# SD.net
KiCad netlist of a schematic drawn in EAGLE
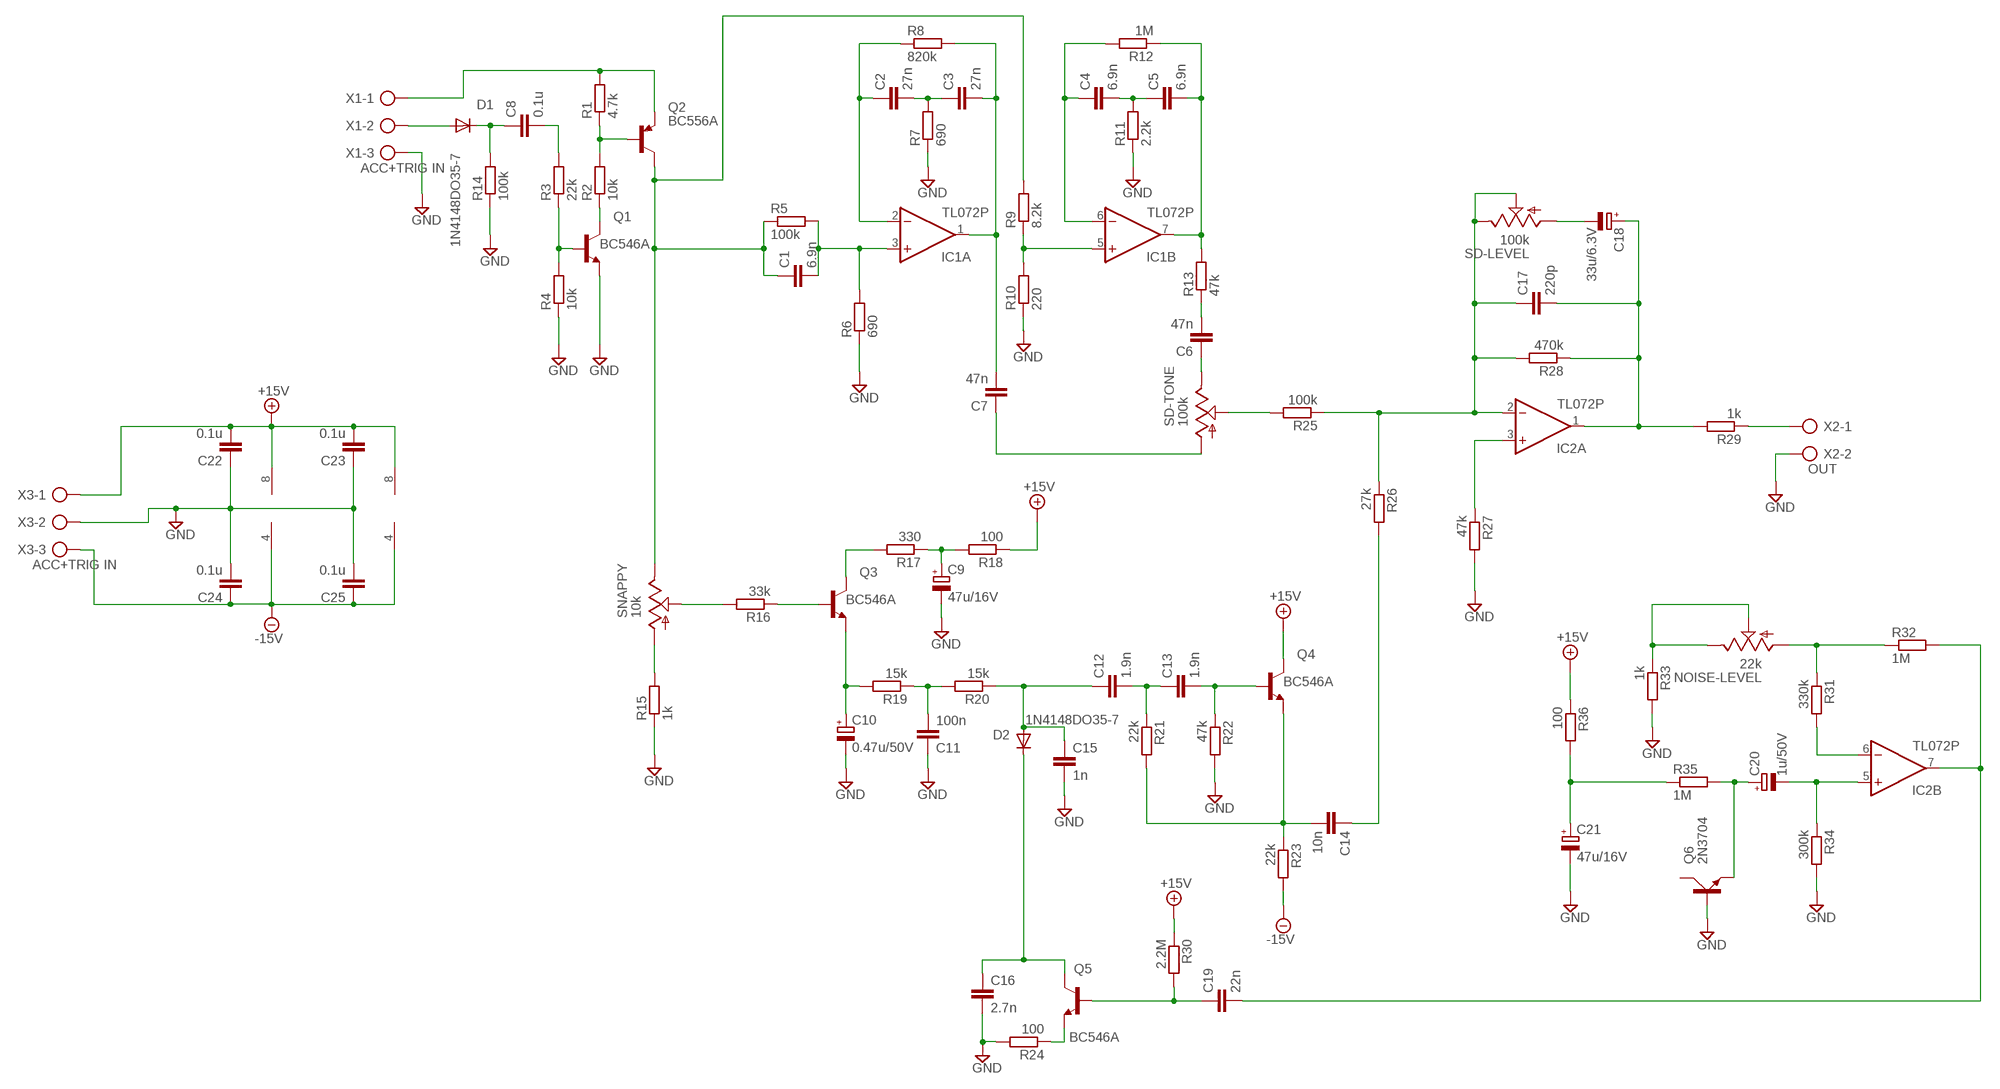
[diagram p0: schematic, sheet 1]

(export (version "E")
  (design (tool "Eeschema 10.0.6"))
  (components
    (comp (ref "C1")
      (value "6.9n")
      (footprint "eagle-import:C075-042X103")
      (libsource (lib "eagle-import") (part "C-EU075-042X103"))
    )
    (comp (ref "C2")
      (value "27n")
      (footprint "eagle-import:C075-042X103")
      (libsource (lib "eagle-import") (part "C-EU075-042X103"))
    )
    (comp (ref "C3")
      (value "27n")
      (footprint "eagle-import:C075-042X103")
      (libsource (lib "eagle-import") (part "C-EU075-042X103"))
    )
    (comp (ref "C4")
      (value "6.9n")
      (footprint "eagle-import:C075-042X103")
      (libsource (lib "eagle-import") (part "C-EU075-042X103"))
    )
    (comp (ref "C5")
      (value "6.9n")
      (footprint "eagle-import:C075-042X103")
      (libsource (lib "eagle-import") (part "C-EU075-042X103"))
    )
    (comp (ref "C6")
      (value "47n")
      (footprint "eagle-import:C075-042X103")
      (libsource (lib "eagle-import") (part "C-EU075-042X103"))
    )
    (comp (ref "C7")
      (value "47n")
      (footprint "eagle-import:C075-042X103")
      (libsource (lib "eagle-import") (part "C-EU075-042X103"))
    )
    (comp (ref "C8")
      (value "0.1u")
      (footprint "eagle-import:C075-042X103")
      (libsource (lib "eagle-import") (part "C-EU075-042X103"))
    )
    (comp (ref "C9")
      (value "47u/16V")
      (footprint "eagle-import:E2-5")
      (libsource (lib "eagle-import") (part "CPOL-EUE2-5"))
    )
    (comp (ref "C10")
      (value "0.47u/50V")
      (footprint "eagle-import:E2-5")
      (libsource (lib "eagle-import") (part "CPOL-EUE2-5"))
    )
    (comp (ref "C11")
      (value "100n")
      (footprint "eagle-import:C075-042X103")
      (libsource (lib "eagle-import") (part "C-EU075-042X103"))
    )
    (comp (ref "C12")
      (value "1.9n")
      (footprint "eagle-import:C075-042X103")
      (libsource (lib "eagle-import") (part "C-EU075-042X103"))
    )
    (comp (ref "C13")
      (value "1.9n")
      (footprint "eagle-import:C075-042X103")
      (libsource (lib "eagle-import") (part "C-EU075-042X103"))
    )
    (comp (ref "C14")
      (value "10n")
      (footprint "eagle-import:C075-042X103")
      (libsource (lib "eagle-import") (part "C-EU075-042X103"))
    )
    (comp (ref "C15")
      (value "1n")
      (footprint "eagle-import:C075-042X103")
      (libsource (lib "eagle-import") (part "C-EU075-042X103"))
    )
    (comp (ref "C16")
      (value "2.7n")
      (footprint "eagle-import:C075-042X103")
      (libsource (lib "eagle-import") (part "C-EU075-042X103"))
    )
    (comp (ref "C17")
      (value "220p")
      (footprint "eagle-import:C075-042X103")
      (libsource (lib "eagle-import") (part "C-EU075-042X103"))
    )
    (comp (ref "C18")
      (value "33u/6.3V")
      (footprint "eagle-import:E2-5")
      (libsource (lib "eagle-import") (part "CPOL-EUE2-5"))
    )
    (comp (ref "C19")
      (value "22n")
      (footprint "eagle-import:C075-042X103")
      (libsource (lib "eagle-import") (part "C-EU075-042X103"))
    )
    (comp (ref "C20")
      (value "1u/50V")
      (footprint "eagle-import:E2-5")
      (libsource (lib "eagle-import") (part "CPOL-EUE2-5"))
    )
    (comp (ref "C21")
      (value "47u/16V")
      (footprint "eagle-import:E2-5")
      (libsource (lib "eagle-import") (part "CPOL-EUE2-5"))
    )
    (comp (ref "C22")
      (value "0.1u")
      (footprint "eagle-import:C075-042X103")
      (libsource (lib "eagle-import") (part "C-EU075-042X103"))
    )
    (comp (ref "C23")
      (value "0.1u")
      (footprint "eagle-import:C075-042X103")
      (libsource (lib "eagle-import") (part "C-EU075-042X103"))
    )
    (comp (ref "C24")
      (value "0.1u")
      (footprint "eagle-import:C075-042X103")
      (libsource (lib "eagle-import") (part "C-EU075-042X103"))
    )
    (comp (ref "C25")
      (value "0.1u")
      (footprint "eagle-import:C075-042X103")
      (libsource (lib "eagle-import") (part "C-EU075-042X103"))
    )
    (comp (ref "D1")
      (value "1N4148DO35-7")
      (footprint "eagle-import:DO35-7")
      (libsource (lib "eagle-import") (part "1N4148DO35-7"))
    )
    (comp (ref "D2")
      (value "1N4148DO35-7")
      (footprint "eagle-import:DO35-7")
      (libsource (lib "eagle-import") (part "1N4148DO35-7"))
    )
    (comp (ref "IC1")
      (value "TL072P")
      (footprint "eagle-import:DIL08")
      (libsource (lib "eagle-import") (part "TL072P"))
    )
    (comp (ref "IC2")
      (value "TL072P")
      (footprint "eagle-import:DIL08")
      (libsource (lib "eagle-import") (part "TL072P"))
    )
    (comp (ref "NOISE-LEVEL")
      (value "22k")
      (footprint "eagle-import:ECP10P")
      (libsource (lib "eagle-import") (part "TRIM_US-ECP10P"))
    )
    (comp (ref "Q1")
      (value "BC546A")
      (footprint "eagle-import:TO92-EBC")
      (libsource (lib "eagle-import") (part "BC546A"))
    )
    (comp (ref "Q2")
      (value "BC556A")
      (footprint "eagle-import:TO92-EBC")
      (libsource (lib "eagle-import") (part "BC556A"))
    )
    (comp (ref "Q3")
      (value "BC546A")
      (footprint "eagle-import:TO92-EBC")
      (libsource (lib "eagle-import") (part "BC546A"))
    )
    (comp (ref "Q4")
      (value "BC546A")
      (footprint "eagle-import:TO92-EBC")
      (libsource (lib "eagle-import") (part "BC546A"))
    )
    (comp (ref "Q5")
      (value "BC546A")
      (footprint "eagle-import:TO92-EBC")
      (libsource (lib "eagle-import") (part "BC546A"))
    )
    (comp (ref "Q6")
      (value "2N3704")
      (footprint "eagle-import:TO92C")
      (libsource (lib "eagle-import") (part "2N3704"))
    )
    (comp (ref "R1")
      (value "4.7k")
      (footprint "eagle-import:0207_10")
      (libsource (lib "eagle-import") (part "R-EU_0207/10"))
    )
    (comp (ref "R2")
      (value "10k")
      (footprint "eagle-import:0207_10")
      (libsource (lib "eagle-import") (part "R-EU_0207/10"))
    )
    (comp (ref "R3")
      (value "22k")
      (footprint "eagle-import:0207_10")
      (libsource (lib "eagle-import") (part "R-EU_0207/10"))
    )
    (comp (ref "R4")
      (value "10k")
      (footprint "eagle-import:0207_10")
      (libsource (lib "eagle-import") (part "R-EU_0207/10"))
    )
    (comp (ref "R5")
      (value "100k")
      (footprint "eagle-import:0207_10")
      (libsource (lib "eagle-import") (part "R-EU_0207/10"))
    )
    (comp (ref "R6")
      (value "690")
      (footprint "eagle-import:0207_10")
      (libsource (lib "eagle-import") (part "R-EU_0207/10"))
    )
    (comp (ref "R7")
      (value "690")
      (footprint "eagle-import:0207_10")
      (libsource (lib "eagle-import") (part "R-EU_0207/10"))
    )
    (comp (ref "R8")
      (value "820k")
      (footprint "eagle-import:0207_10")
      (libsource (lib "eagle-import") (part "R-EU_0207/10"))
    )
    (comp (ref "R9")
      (value "8.2k")
      (footprint "eagle-import:0207_10")
      (libsource (lib "eagle-import") (part "R-EU_0207/10"))
    )
    (comp (ref "R10")
      (value "220")
      (footprint "eagle-import:0207_10")
      (libsource (lib "eagle-import") (part "R-EU_0207/10"))
    )
    (comp (ref "R11")
      (value "2.2k")
      (footprint "eagle-import:0207_10")
      (libsource (lib "eagle-import") (part "R-EU_0207/10"))
    )
    (comp (ref "R12")
      (value "1M")
      (footprint "eagle-import:0207_10")
      (libsource (lib "eagle-import") (part "R-EU_0207/10"))
    )
    (comp (ref "R13")
      (value "47k")
      (footprint "eagle-import:0207_10")
      (libsource (lib "eagle-import") (part "R-EU_0207/10"))
    )
    (comp (ref "R14")
      (value "100k")
      (footprint "eagle-import:0207_10")
      (libsource (lib "eagle-import") (part "R-EU_0207/10"))
    )
    (comp (ref "R15")
      (value "1k")
      (footprint "eagle-import:0207_10")
      (libsource (lib "eagle-import") (part "R-EU_0207/10"))
    )
    (comp (ref "R16")
      (value "33k")
      (footprint "eagle-import:0207_10")
      (libsource (lib "eagle-import") (part "R-EU_0207/10"))
    )
    (comp (ref "R17")
      (value "330")
      (footprint "eagle-import:0207_10")
      (libsource (lib "eagle-import") (part "R-EU_0207/10"))
    )
    (comp (ref "R18")
      (value "100")
      (footprint "eagle-import:0207_10")
      (libsource (lib "eagle-import") (part "R-EU_0207/10"))
    )
    (comp (ref "R19")
      (value "15k")
      (footprint "eagle-import:0207_10")
      (libsource (lib "eagle-import") (part "R-EU_0207/10"))
    )
    (comp (ref "R20")
      (value "15k")
      (footprint "eagle-import:0207_10")
      (libsource (lib "eagle-import") (part "R-EU_0207/10"))
    )
    (comp (ref "R21")
      (value "22k")
      (footprint "eagle-import:0207_10")
      (libsource (lib "eagle-import") (part "R-EU_0207/10"))
    )
    (comp (ref "R22")
      (value "47k")
      (footprint "eagle-import:0207_10")
      (libsource (lib "eagle-import") (part "R-EU_0207/10"))
    )
    (comp (ref "R23")
      (value "22k")
      (footprint "eagle-import:0207_10")
      (libsource (lib "eagle-import") (part "R-EU_0207/10"))
    )
    (comp (ref "R24")
      (value "100")
      (footprint "eagle-import:0207_10")
      (libsource (lib "eagle-import") (part "R-EU_0207/10"))
    )
    (comp (ref "R25")
      (value "100k")
      (footprint "eagle-import:0207_10")
      (libsource (lib "eagle-import") (part "R-EU_0207/10"))
    )
    (comp (ref "R26")
      (value "27k")
      (footprint "eagle-import:0207_10")
      (libsource (lib "eagle-import") (part "R-EU_0207/10"))
    )
    (comp (ref "R27")
      (value "47k")
      (footprint "eagle-import:0207_10")
      (libsource (lib "eagle-import") (part "R-EU_0207/10"))
    )
    (comp (ref "R28")
      (value "470k")
      (footprint "eagle-import:0207_10")
      (libsource (lib "eagle-import") (part "R-EU_0207/10"))
    )
    (comp (ref "R29")
      (value "1k")
      (footprint "eagle-import:0207_10")
      (libsource (lib "eagle-import") (part "R-EU_0207/10"))
    )
    (comp (ref "R30")
      (value "2.2M")
      (footprint "eagle-import:0207_10")
      (libsource (lib "eagle-import") (part "R-EU_0207/10"))
    )
    (comp (ref "R31")
      (value "330k")
      (footprint "eagle-import:0207_10")
      (libsource (lib "eagle-import") (part "R-EU_0207/10"))
    )
    (comp (ref "R32")
      (value "1M")
      (footprint "eagle-import:0207_10")
      (libsource (lib "eagle-import") (part "R-EU_0207/10"))
    )
    (comp (ref "R33")
      (value "1k")
      (footprint "eagle-import:0207_10")
      (libsource (lib "eagle-import") (part "R-EU_0207/10"))
    )
    (comp (ref "R34")
      (value "300k")
      (footprint "eagle-import:0207_10")
      (libsource (lib "eagle-import") (part "R-EU_0207/10"))
    )
    (comp (ref "R35")
      (value "1M")
      (footprint "eagle-import:0207_10")
      (libsource (lib "eagle-import") (part "R-EU_0207/10"))
    )
    (comp (ref "R36")
      (value "100")
      (footprint "eagle-import:0207_10")
      (libsource (lib "eagle-import") (part "R-EU_0207/10"))
    )
    (comp (ref "SD-LEVEL")
      (value "100k")
      (footprint "eagle-import:ECP10P")
      (libsource (lib "eagle-import") (part "TRIM_US-ECP10P"))
    )
    (comp (ref "SD-TONE")
      (value "100k")
      (footprint "eagle-import:ECP10P")
      (libsource (lib "eagle-import") (part "TRIM_US-ECP10P"))
    )
    (comp (ref "SNAPPY")
      (value "10k")
      (footprint "eagle-import:ECP10P")
      (libsource (lib "eagle-import") (part "TRIM_US-ECP10P"))
    )
    (comp (ref "X1")
      (value "ACC+TRIG IN")
      (footprint "eagle-import:AK300_3")
      (libsource (lib "eagle-import") (part "AK300/3"))
    )
    (comp (ref "X2")
      (value "OUT")
      (footprint "eagle-import:AK300_2")
      (libsource (lib "eagle-import") (part "AK300/2"))
    )
    (comp (ref "X3")
      (value "ACC+TRIG IN")
      (footprint "eagle-import:AK300_3")
      (libsource (lib "eagle-import") (part "AK300/3"))
    )
  )
  (nets
    (net (code "1") (name "+15V") (class "Default")
      (node (ref "C22") (pin "2") (pinfunction "2_2") (pintype "passive"))
      (node (ref "C23") (pin "2") (pinfunction "2_2") (pintype "passive"))
      (node (ref "IC1") (pin "8") (pinfunction "V+_8") (pintype "power_in"))
      (node (ref "IC2") (pin "8") (pinfunction "V+_8") (pintype "power_in"))
      (node (ref "Q4") (pin "C") (pinfunction "C_C") (pintype "passive"))
      (node (ref "R18") (pin "1") (pinfunction "1_1") (pintype "passive"))
      (node (ref "R30") (pin "1") (pinfunction "1_1") (pintype "passive"))
      (node (ref "R36") (pin "1") (pinfunction "1_1") (pintype "passive"))
      (node (ref "X3") (pin "1") (pinfunction "KL_1") (pintype "passive"))
    )
    (net (code "2") (name "-15V") (class "Default")
      (node (ref "C24") (pin "1") (pinfunction "1_1") (pintype "passive"))
      (node (ref "C25") (pin "1") (pinfunction "1_1") (pintype "passive"))
      (node (ref "IC1") (pin "4") (pinfunction "V-_4") (pintype "power_in"))
      (node (ref "IC2") (pin "4") (pinfunction "V-_4") (pintype "power_in"))
      (node (ref "R23") (pin "2") (pinfunction "2_2") (pintype "passive"))
      (node (ref "X3") (pin "3") (pinfunction "KL_3") (pintype "passive"))
    )
    (net (code "3") (name "GND") (class "Default")
      (node (ref "C10") (pin "-") (pinfunction "-_-") (pintype "passive"))
      (node (ref "C11") (pin "1") (pinfunction "1_1") (pintype "passive"))
      (node (ref "C15") (pin "2") (pinfunction "2_2") (pintype "passive"))
      (node (ref "C16") (pin "2") (pinfunction "2_2") (pintype "passive"))
      (node (ref "C21") (pin "-") (pinfunction "-_-") (pintype "passive"))
      (node (ref "C22") (pin "1") (pinfunction "1_1") (pintype "passive"))
      (node (ref "C23") (pin "1") (pinfunction "1_1") (pintype "passive"))
      (node (ref "C24") (pin "2") (pinfunction "2_2") (pintype "passive"))
      (node (ref "C25") (pin "2") (pinfunction "2_2") (pintype "passive"))
      (node (ref "C9") (pin "-") (pinfunction "-_-") (pintype "passive"))
      (node (ref "Q1") (pin "E") (pinfunction "E_E") (pintype "passive"))
      (node (ref "Q6") (pin "B") (pinfunction "B_B") (pintype "passive"))
      (node (ref "R10") (pin "1") (pinfunction "1_1") (pintype "passive"))
      (node (ref "R11") (pin "1") (pinfunction "1_1") (pintype "passive"))
      (node (ref "R14") (pin "1") (pinfunction "1_1") (pintype "passive"))
      (node (ref "R15") (pin "1") (pinfunction "1_1") (pintype "passive"))
      (node (ref "R22") (pin "2") (pinfunction "2_2") (pintype "passive"))
      (node (ref "R24") (pin "2") (pinfunction "2_2") (pintype "passive"))
      (node (ref "R27") (pin "2") (pinfunction "2_2") (pintype "passive"))
      (node (ref "R33") (pin "2") (pinfunction "2_2") (pintype "passive"))
      (node (ref "R34") (pin "2") (pinfunction "2_2") (pintype "passive"))
      (node (ref "R4") (pin "1") (pinfunction "1_1") (pintype "passive"))
      (node (ref "R6") (pin "1") (pinfunction "1_1") (pintype "passive"))
      (node (ref "R7") (pin "1") (pinfunction "1_1") (pintype "passive"))
      (node (ref "X1") (pin "3") (pinfunction "KL_3") (pintype "passive"))
      (node (ref "X2") (pin "2") (pinfunction "KL_2") (pintype "passive"))
      (node (ref "X3") (pin "2") (pinfunction "KL_2") (pintype "passive"))
    )
    (net (code "4") (name "Net-(C1-Pad1)") (class "Default")
      (node (ref "C1") (pin "1") (pinfunction "1_1") (pintype "passive"))
      (node (ref "Q2") (pin "C") (pinfunction "C_C") (pintype "passive"))
      (node (ref "R5") (pin "1") (pinfunction "1_1") (pintype "passive"))
      (node (ref "R9") (pin "2") (pinfunction "2_2") (pintype "passive"))
      (node (ref "SNAPPY") (pin "E") (pinfunction "E_E") (pintype "passive"))
    )
    (net (code "5") (name "Net-(C2-Pad2)") (class "Default")
      (node (ref "C2") (pin "2") (pinfunction "2_2") (pintype "passive"))
      (node (ref "C3") (pin "1") (pinfunction "1_1") (pintype "passive"))
      (node (ref "R7") (pin "2") (pinfunction "2_2") (pintype "passive"))
    )
    (net (code "6") (name "Net-(C4-Pad2)") (class "Default")
      (node (ref "C4") (pin "2") (pinfunction "2_2") (pintype "passive"))
      (node (ref "C5") (pin "1") (pinfunction "1_1") (pintype "passive"))
      (node (ref "R11") (pin "2") (pinfunction "2_2") (pintype "passive"))
    )
    (net (code "7") (name "Net-(C6-Pad1)") (class "Default")
      (node (ref "C6") (pin "1") (pinfunction "1_1") (pintype "passive"))
      (node (ref "SD-TONE") (pin "E") (pinfunction "E_E") (pintype "passive"))
    )
    (net (code "8") (name "Net-(C6-Pad2)") (class "Default")
      (node (ref "C6") (pin "2") (pinfunction "2_2") (pintype "passive"))
      (node (ref "R13") (pin "1") (pinfunction "1_1") (pintype "passive"))
    )
    (net (code "9") (name "Net-(C7-Pad1)") (class "Default")
      (node (ref "C7") (pin "1") (pinfunction "1_1") (pintype "passive"))
      (node (ref "SD-TONE") (pin "A") (pinfunction "A_A") (pintype "passive"))
    )
    (net (code "10") (name "Net-(C8-Pad1)") (class "Default")
      (node (ref "C8") (pin "1") (pinfunction "1_1") (pintype "passive"))
      (node (ref "D1") (pin "C") (pinfunction "C_C") (pintype "passive"))
      (node (ref "R14") (pin "2") (pinfunction "2_2") (pintype "passive"))
    )
    (net (code "11") (name "Net-(C8-Pad2)") (class "Default")
      (node (ref "C8") (pin "2") (pinfunction "2_2") (pintype "passive"))
      (node (ref "R3") (pin "2") (pinfunction "2_2") (pintype "passive"))
    )
    (net (code "12") (name "Net-(C9-Pad+)") (class "Default")
      (node (ref "C9") (pin "+") (pinfunction "+_+") (pintype "passive"))
      (node (ref "R17") (pin "1") (pinfunction "1_1") (pintype "passive"))
      (node (ref "R18") (pin "2") (pinfunction "2_2") (pintype "passive"))
    )
    (net (code "13") (name "Net-(C10-Pad+)") (class "Default")
      (node (ref "C10") (pin "+") (pinfunction "+_+") (pintype "passive"))
      (node (ref "Q3") (pin "E") (pinfunction "E_E") (pintype "passive"))
      (node (ref "R19") (pin "2") (pinfunction "2_2") (pintype "passive"))
    )
    (net (code "14") (name "Net-(C11-Pad2)") (class "Default")
      (node (ref "C11") (pin "2") (pinfunction "2_2") (pintype "passive"))
      (node (ref "R19") (pin "1") (pinfunction "1_1") (pintype "passive"))
      (node (ref "R20") (pin "2") (pinfunction "2_2") (pintype "passive"))
    )
    (net (code "15") (name "Net-(C12-Pad1)") (class "Default")
      (node (ref "C12") (pin "1") (pinfunction "1_1") (pintype "passive"))
      (node (ref "C15") (pin "1") (pinfunction "1_1") (pintype "passive"))
      (node (ref "D2") (pin "A") (pinfunction "A_A") (pintype "passive"))
      (node (ref "R20") (pin "1") (pinfunction "1_1") (pintype "passive"))
    )
    (net (code "16") (name "Net-(C12-Pad2)") (class "Default")
      (node (ref "C12") (pin "2") (pinfunction "2_2") (pintype "passive"))
      (node (ref "C13") (pin "1") (pinfunction "1_1") (pintype "passive"))
      (node (ref "R21") (pin "1") (pinfunction "1_1") (pintype "passive"))
    )
    (net (code "17") (name "Net-(C13-Pad2)") (class "Default")
      (node (ref "C13") (pin "2") (pinfunction "2_2") (pintype "passive"))
      (node (ref "Q4") (pin "B") (pinfunction "B_B") (pintype "passive"))
      (node (ref "R22") (pin "1") (pinfunction "1_1") (pintype "passive"))
    )
    (net (code "18") (name "Net-(C14-Pad1)") (class "Default")
      (node (ref "C14") (pin "1") (pinfunction "1_1") (pintype "passive"))
      (node (ref "R26") (pin "2") (pinfunction "2_2") (pintype "passive"))
    )
    (net (code "19") (name "Net-(C14-Pad2)") (class "Default")
      (node (ref "C14") (pin "2") (pinfunction "2_2") (pintype "passive"))
      (node (ref "Q4") (pin "E") (pinfunction "E_E") (pintype "passive"))
      (node (ref "R21") (pin "2") (pinfunction "2_2") (pintype "passive"))
      (node (ref "R23") (pin "1") (pinfunction "1_1") (pintype "passive"))
    )
    (net (code "20") (name "Net-(C16-Pad1)") (class "Default")
      (node (ref "C16") (pin "1") (pinfunction "1_1") (pintype "passive"))
      (node (ref "D2") (pin "C") (pinfunction "C_C") (pintype "passive"))
      (node (ref "Q5") (pin "C") (pinfunction "C_C") (pintype "passive"))
    )
    (net (code "21") (name "Net-(C18-Pad-)") (class "Default")
      (node (ref "C18") (pin "-") (pinfunction "-_-") (pintype "passive"))
      (node (ref "SD-LEVEL") (pin "A") (pinfunction "A_A") (pintype "passive"))
    )
    (net (code "22") (name "Net-(C19-Pad1)") (class "Default")
      (node (ref "C19") (pin "1") (pinfunction "1_1") (pintype "passive"))
      (node (ref "Q5") (pin "B") (pinfunction "B_B") (pintype "passive"))
      (node (ref "R30") (pin "2") (pinfunction "2_2") (pintype "passive"))
    )
    (net (code "23") (name "Net-(C20-Pad+)") (class "Default")
      (node (ref "C20") (pin "+") (pinfunction "+_+") (pintype "passive"))
      (node (ref "Q6") (pin "E") (pinfunction "E_E") (pintype "passive"))
      (node (ref "R35") (pin "2") (pinfunction "2_2") (pintype "passive"))
    )
    (net (code "24") (name "Net-(C21-Pad+)") (class "Default")
      (node (ref "C21") (pin "+") (pinfunction "+_+") (pintype "passive"))
      (node (ref "R35") (pin "1") (pinfunction "1_1") (pintype "passive"))
      (node (ref "R36") (pin "2") (pinfunction "2_2") (pintype "passive"))
    )
    (net (code "25") (name "Net-(IC1A-+IN)") (class "Default")
      (node (ref "C1") (pin "2") (pinfunction "2_2") (pintype "passive"))
      (node (ref "IC1") (pin "3") (pinfunction "+IN_3") (pintype "input"))
      (node (ref "R5") (pin "2") (pinfunction "2_2") (pintype "passive"))
      (node (ref "R6") (pin "2") (pinfunction "2_2") (pintype "passive"))
    )
    (net (code "26") (name "Net-(IC1A--IN)") (class "Default")
      (node (ref "C2") (pin "1") (pinfunction "1_1") (pintype "passive"))
      (node (ref "IC1") (pin "2") (pinfunction "-IN_2") (pintype "input"))
      (node (ref "R8") (pin "1") (pinfunction "1_1") (pintype "passive"))
    )
    (net (code "27") (name "Net-(IC1A-OUT)") (class "Default")
      (node (ref "C3") (pin "2") (pinfunction "2_2") (pintype "passive"))
      (node (ref "C7") (pin "2") (pinfunction "2_2") (pintype "passive"))
      (node (ref "IC1") (pin "1") (pinfunction "OUT_1") (pintype "output"))
      (node (ref "R8") (pin "2") (pinfunction "2_2") (pintype "passive"))
    )
    (net (code "28") (name "Net-(IC1B-+IN)") (class "Default")
      (node (ref "IC1") (pin "5") (pinfunction "+IN_5") (pintype "input"))
      (node (ref "R10") (pin "2") (pinfunction "2_2") (pintype "passive"))
      (node (ref "R9") (pin "1") (pinfunction "1_1") (pintype "passive"))
    )
    (net (code "29") (name "Net-(IC1B--IN)") (class "Default")
      (node (ref "C4") (pin "1") (pinfunction "1_1") (pintype "passive"))
      (node (ref "IC1") (pin "6") (pinfunction "-IN_6") (pintype "input"))
      (node (ref "R12") (pin "2") (pinfunction "2_2") (pintype "passive"))
    )
    (net (code "30") (name "Net-(IC1B-OUT)") (class "Default")
      (node (ref "C5") (pin "2") (pinfunction "2_2") (pintype "passive"))
      (node (ref "IC1") (pin "7") (pinfunction "OUT_7") (pintype "output"))
      (node (ref "R12") (pin "1") (pinfunction "1_1") (pintype "passive"))
      (node (ref "R13") (pin "2") (pinfunction "2_2") (pintype "passive"))
    )
    (net (code "31") (name "Net-(IC2A-+IN)") (class "Default")
      (node (ref "IC2") (pin "3") (pinfunction "+IN_3") (pintype "input"))
      (node (ref "R27") (pin "1") (pinfunction "1_1") (pintype "passive"))
    )
    (net (code "32") (name "Net-(IC2A--IN)") (class "Default")
      (node (ref "C17") (pin "1") (pinfunction "1_1") (pintype "passive"))
      (node (ref "IC2") (pin "2") (pinfunction "-IN_2") (pintype "input"))
      (node (ref "R25") (pin "1") (pinfunction "1_1") (pintype "passive"))
      (node (ref "R26") (pin "1") (pinfunction "1_1") (pintype "passive"))
      (node (ref "R28") (pin "2") (pinfunction "2_2") (pintype "passive"))
      (node (ref "SD-LEVEL") (pin "E") (pinfunction "E_E") (pintype "passive"))
      (node (ref "SD-LEVEL") (pin "S") (pinfunction "S_S") (pintype "passive"))
    )
    (net (code "33") (name "Net-(IC2A-OUT)") (class "Default")
      (node (ref "C17") (pin "2") (pinfunction "2_2") (pintype "passive"))
      (node (ref "C18") (pin "+") (pinfunction "+_+") (pintype "passive"))
      (node (ref "IC2") (pin "1") (pinfunction "OUT_1") (pintype "output"))
      (node (ref "R28") (pin "1") (pinfunction "1_1") (pintype "passive"))
      (node (ref "R29") (pin "2") (pinfunction "2_2") (pintype "passive"))
    )
    (net (code "34") (name "Net-(IC2B-+IN)") (class "Default")
      (node (ref "C20") (pin "-") (pinfunction "-_-") (pintype "passive"))
      (node (ref "IC2") (pin "5") (pinfunction "+IN_5") (pintype "input"))
      (node (ref "R34") (pin "1") (pinfunction "1_1") (pintype "passive"))
    )
    (net (code "35") (name "Net-(IC2B--IN)") (class "Default")
      (node (ref "IC2") (pin "6") (pinfunction "-IN_6") (pintype "input"))
      (node (ref "R31") (pin "2") (pinfunction "2_2") (pintype "passive"))
    )
    (net (code "36") (name "Net-(IC2B-OUT)") (class "Default")
      (node (ref "C19") (pin "2") (pinfunction "2_2") (pintype "passive"))
      (node (ref "IC2") (pin "7") (pinfunction "OUT_7") (pintype "output"))
      (node (ref "R32") (pin "2") (pinfunction "2_2") (pintype "passive"))
    )
    (net (code "37") (name "Net-(NOISE-LEVEL-PadA)") (class "Default")
      (node (ref "NOISE-LEVEL") (pin "A") (pinfunction "A_A") (pintype "passive"))
      (node (ref "R31") (pin "1") (pinfunction "1_1") (pintype "passive"))
      (node (ref "R32") (pin "1") (pinfunction "1_1") (pintype "passive"))
    )
    (net (code "38") (name "Net-(NOISE-LEVEL-PadE)") (class "Default")
      (node (ref "NOISE-LEVEL") (pin "E") (pinfunction "E_E") (pintype "passive"))
      (node (ref "NOISE-LEVEL") (pin "S") (pinfunction "S_S") (pintype "passive"))
      (node (ref "R33") (pin "1") (pinfunction "1_1") (pintype "passive"))
    )
    (net (code "39") (name "Net-(Q1-PadB)") (class "Default")
      (node (ref "Q1") (pin "B") (pinfunction "B_B") (pintype "passive"))
      (node (ref "R3") (pin "1") (pinfunction "1_1") (pintype "passive"))
      (node (ref "R4") (pin "2") (pinfunction "2_2") (pintype "passive"))
    )
    (net (code "40") (name "Net-(Q1-PadC)") (class "Default")
      (node (ref "Q1") (pin "C") (pinfunction "C_C") (pintype "passive"))
      (node (ref "R2") (pin "1") (pinfunction "1_1") (pintype "passive"))
    )
    (net (code "41") (name "Net-(Q2-PadB)") (class "Default")
      (node (ref "Q2") (pin "B") (pinfunction "B_B") (pintype "passive"))
      (node (ref "R1") (pin "1") (pinfunction "1_1") (pintype "passive"))
      (node (ref "R2") (pin "2") (pinfunction "2_2") (pintype "passive"))
    )
    (net (code "42") (name "Net-(Q3-PadB)") (class "Default")
      (node (ref "Q3") (pin "B") (pinfunction "B_B") (pintype "passive"))
      (node (ref "R16") (pin "1") (pinfunction "1_1") (pintype "passive"))
    )
    (net (code "43") (name "Net-(Q3-PadC)") (class "Default")
      (node (ref "Q3") (pin "C") (pinfunction "C_C") (pintype "passive"))
      (node (ref "R17") (pin "2") (pinfunction "2_2") (pintype "passive"))
    )
    (net (code "44") (name "Net-(Q5-PadE)") (class "Default")
      (node (ref "Q5") (pin "E") (pinfunction "E_E") (pintype "passive"))
      (node (ref "R24") (pin "1") (pinfunction "1_1") (pintype "passive"))
    )
    (net (code "45") (name "Net-(R15-Pad2)") (class "Default")
      (node (ref "R15") (pin "2") (pinfunction "2_2") (pintype "passive"))
      (node (ref "SNAPPY") (pin "A") (pinfunction "A_A") (pintype "passive"))
    )
    (net (code "46") (name "Net-(R16-Pad2)") (class "Default")
      (node (ref "R16") (pin "2") (pinfunction "2_2") (pintype "passive"))
      (node (ref "SNAPPY") (pin "S") (pinfunction "S_S") (pintype "passive"))
    )
    (net (code "47") (name "Net-(R25-Pad2)") (class "Default")
      (node (ref "R25") (pin "2") (pinfunction "2_2") (pintype "passive"))
      (node (ref "SD-TONE") (pin "S") (pinfunction "S_S") (pintype "passive"))
    )
    (net (code "48") (name "Net-(X1A-KL)") (class "Default")
      (node (ref "Q2") (pin "E") (pinfunction "E_E") (pintype "passive"))
      (node (ref "R1") (pin "2") (pinfunction "2_2") (pintype "passive"))
      (node (ref "X1") (pin "1") (pinfunction "KL_1") (pintype "passive"))
    )
    (net (code "49") (name "Net-(X1B-KL)") (class "Default")
      (node (ref "D1") (pin "A") (pinfunction "A_A") (pintype "passive"))
      (node (ref "X1") (pin "2") (pinfunction "KL_2") (pintype "passive"))
    )
    (net (code "50") (name "Net-(X2A-KL)") (class "Default")
      (node (ref "R29") (pin "1") (pinfunction "1_1") (pintype "passive"))
      (node (ref "X2") (pin "1") (pinfunction "KL_1") (pintype "passive"))
    )
    (net (code "51") (name "unconnected-(Q6-PadC)") (class "Default")
      (node (ref "Q6") (pin "C") (pinfunction "C_C") (pintype "passive"))
    )
  )
)
